# Peripherals.net
KiCad netlist of a schematic drawn in Altium Designer
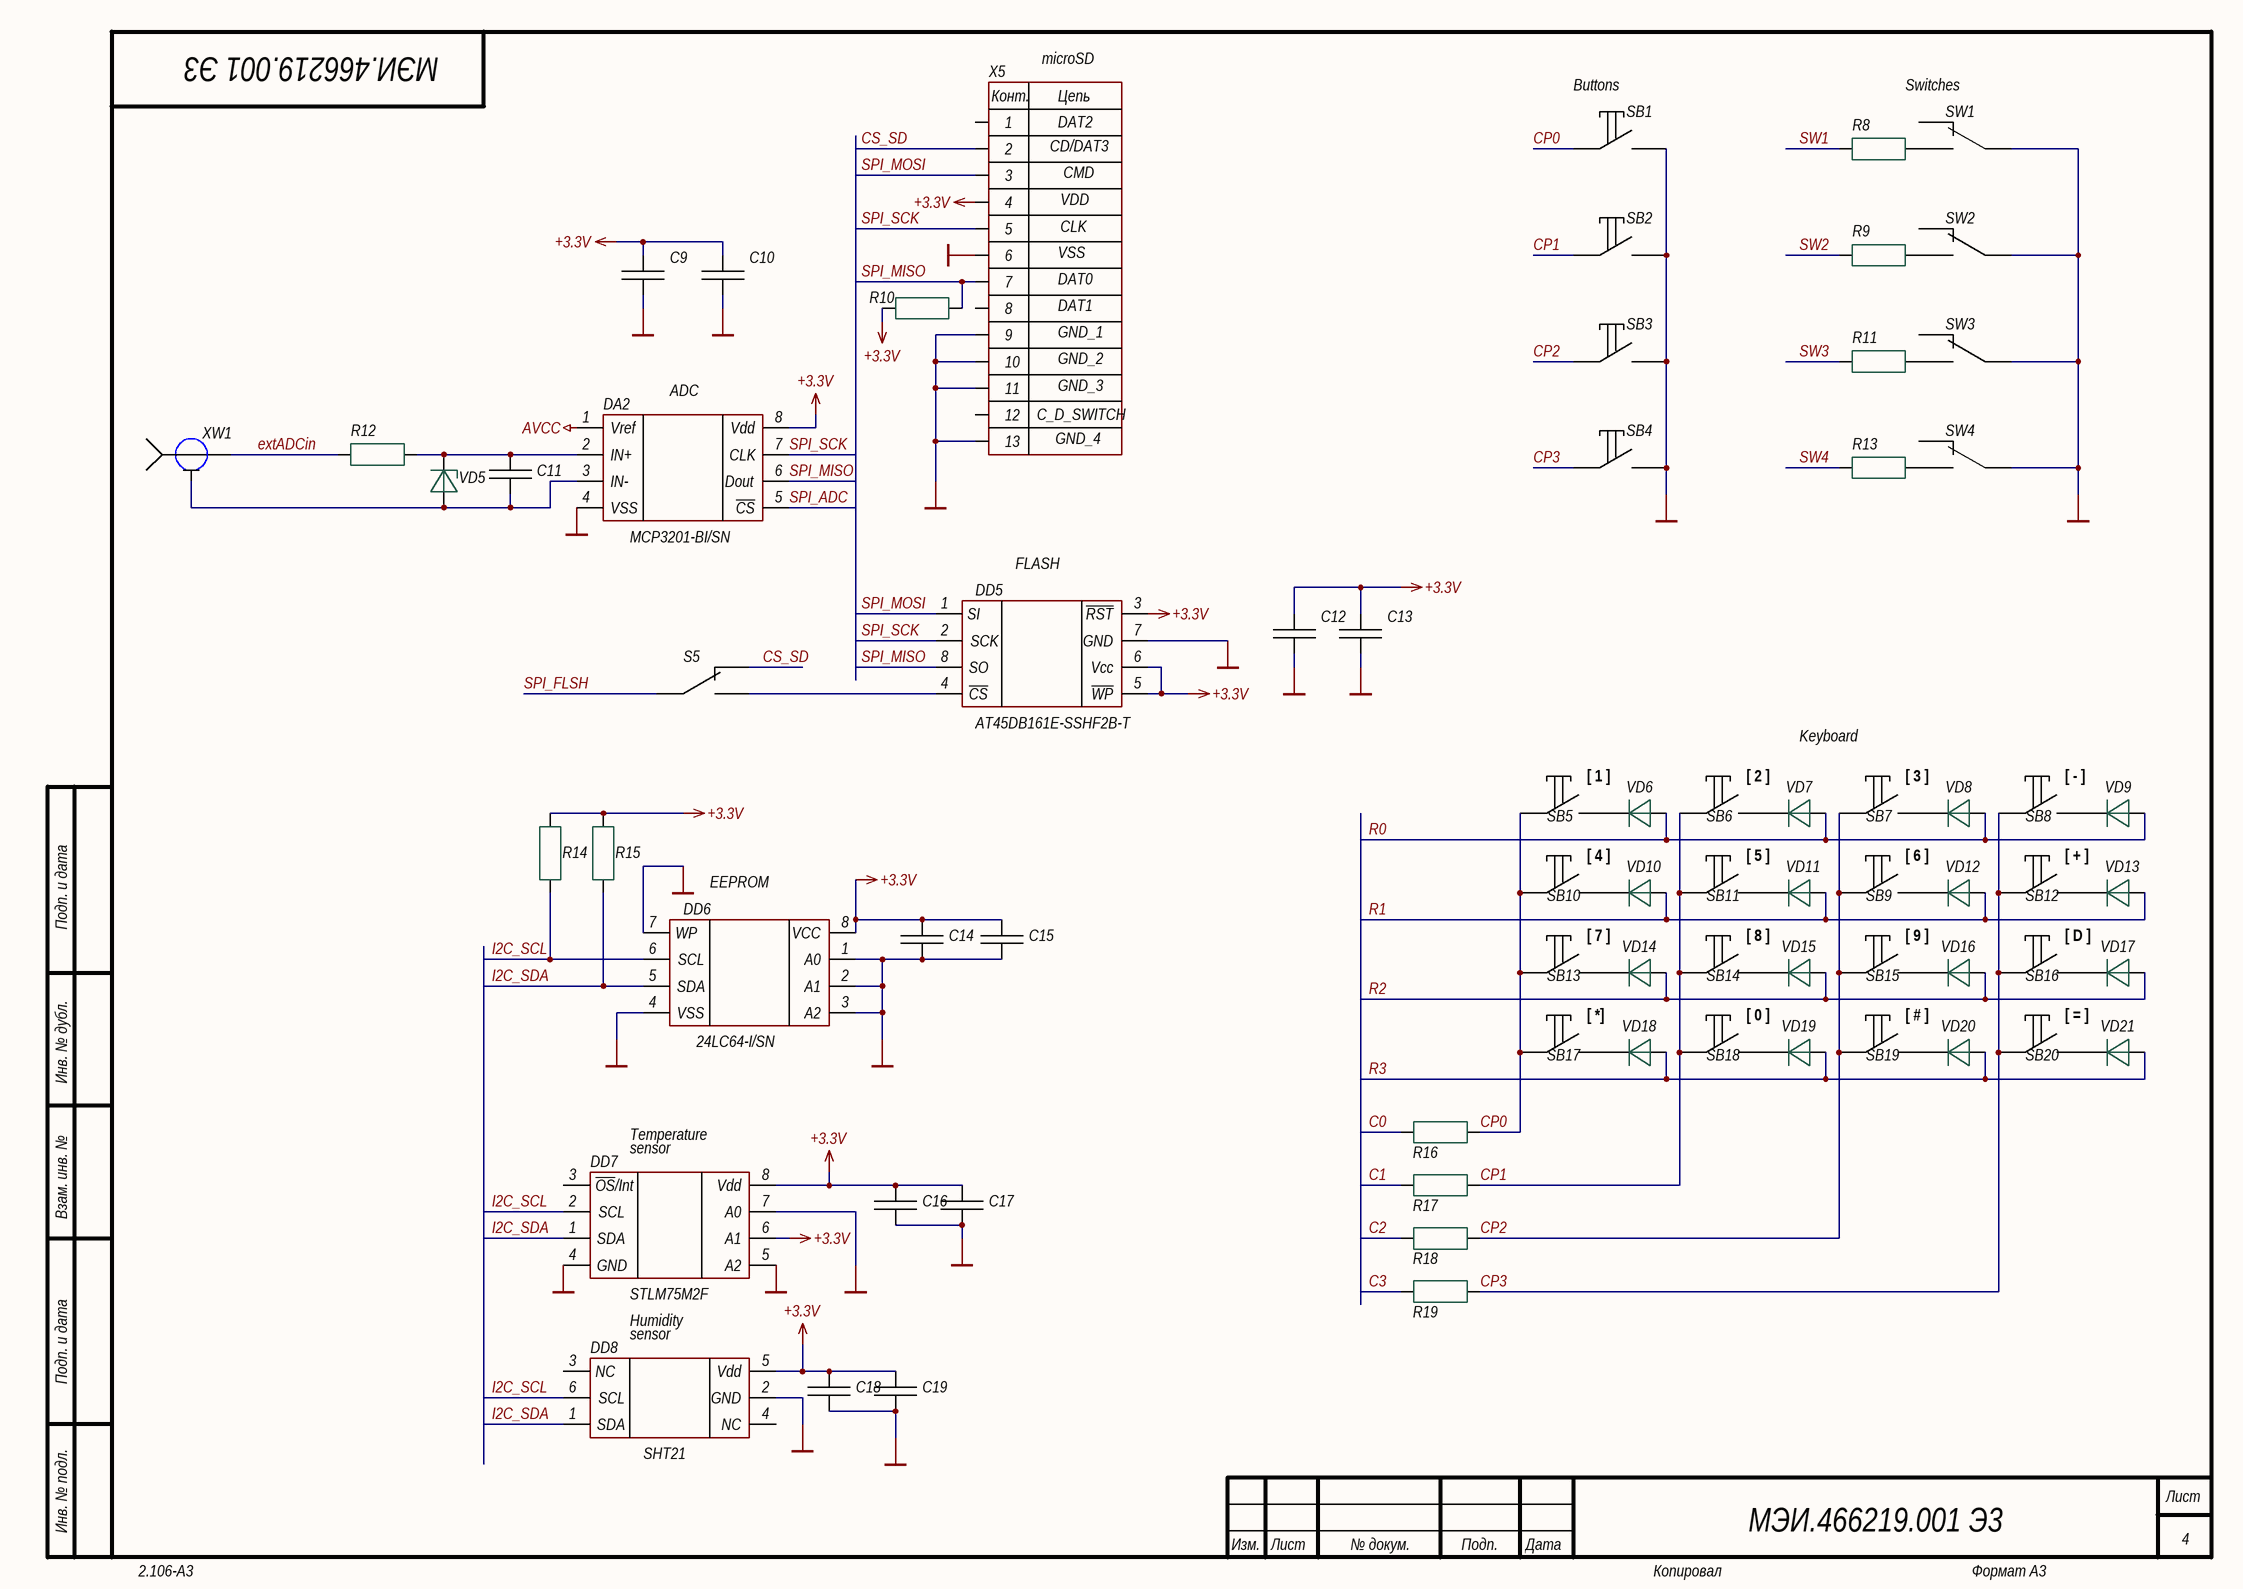
[diagram p0: Peripherals.SchDoc]

(export (version "E")
  (design (tool "Eeschema 10.0.6"))
  (components
    (comp (ref "C9")
      (value "approved sub OK")
      (footprint "CAPC1608X90N")
      (description "Capacitor SMD Cer 100nF 10% 50V X7R 0603")
      (fields (field (name "TOLERANCE") "±10%"))
      (libsource (lib "PBL - Capacitors") (part "CAPC_100n_0603_X7R_50V_10%"))
    )
    (comp (ref "C10")
      (value "approved sub OK")
      (footprint "PBL - SMD Packages:CAPC1608X90N")
      (description "Capacitor SMD Cer 10uF 10% 10V X5R 0603")
      (fields (field (name "TOLERANCE") "±10%"))
      (libsource (lib "PBL - Capacitors") (part "CAPC_10u_0805_10V"))
    )
    (comp (ref "C11")
      (value "approved sub OK")
      (footprint "CAPC2012X135N")
      (description "Capacitor SMD Cer 330nF 10% 25V X7R 0805")
      (fields (field (name "TOLERANCE") "±10%"))
      (libsource (lib "PBL - Capacitors") (part "CAPC_330n_0805_X7R_25V_10%"))
    )
    (comp (ref "C12")
      (value "approved sub OK")
      (footprint "CAPC1608X90N")
      (description "Capacitor SMD Cer 100nF 10% 50V X7R 0603")
      (fields (field (name "TOLERANCE") "±10%"))
      (libsource (lib "PBL - Capacitors") (part "CAPC_100n_0603_X7R_50V_10%"))
    )
    (comp (ref "C13")
      (value "approved sub OK")
      (footprint "PBL - SMD Packages:CAPC1608X90N")
      (description "Capacitor SMD Cer 10uF 10% 10V X5R 0603")
      (fields (field (name "TOLERANCE") "±10%"))
      (libsource (lib "PBL - Capacitors") (part "CAPC_10u_0805_10V"))
    )
    (comp (ref "C14")
      (value "approved sub OK")
      (footprint "CAPC1608X90N")
      (description "Capacitor SMD Cer 100nF 10% 50V X7R 0603")
      (fields (field (name "TOLERANCE") "±10%"))
      (libsource (lib "PBL - Capacitors") (part "CAPC_100n_0603_X7R_50V_10%"))
    )
    (comp (ref "C15")
      (value "approved sub OK")
      (footprint "PBL - SMD Packages:CAPC1608X90N")
      (description "Capacitor SMD Cer 10uF 10% 10V X5R 0603")
      (fields (field (name "TOLERANCE") "±10%"))
      (libsource (lib "PBL - Capacitors") (part "CAPC_10u_0805_10V"))
    )
    (comp (ref "C16")
      (value "approved sub OK")
      (footprint "CAPC1608X90N")
      (description "Capacitor SMD Cer 100nF 10% 50V X7R 0603")
      (fields (field (name "TOLERANCE") "±10%"))
      (libsource (lib "PBL - Capacitors") (part "CAPC_100n_0603_X7R_50V_10%"))
    )
    (comp (ref "C17")
      (value "approved sub OK")
      (footprint "PBL - SMD Packages:CAPC1608X90N")
      (description "Capacitor SMD Cer 10uF 10% 10V X5R 0603")
      (fields (field (name "TOLERANCE") "±10%"))
      (libsource (lib "PBL - Capacitors") (part "CAPC_10u_0805_10V"))
    )
    (comp (ref "C18")
      (value "approved sub OK")
      (footprint "CAPC1608X90N")
      (description "Capacitor SMD Cer 100nF 10% 50V X7R 0603")
      (fields (field (name "TOLERANCE") "±10%"))
      (libsource (lib "PBL - Capacitors") (part "CAPC_100n_0603_X7R_50V_10%"))
    )
    (comp (ref "C19")
      (value "approved sub OK")
      (footprint "PBL - SMD Packages:CAPC1608X90N")
      (description "Capacitor SMD Cer 10uF 10% 10V X5R 0603")
      (fields (field (name "TOLERANCE") "±10%"))
      (libsource (lib "PBL - Capacitors") (part "CAPC_10u_0805_10V"))
    )
    (comp (ref "DA2")
      (value "MCP3201-BI/SN")
      (footprint "PBL - SMD Packages:SOIC127P600X175-8AN")
      (description "ADC")
      (fields (field (name "MODEL") "MCP3201-BI/SN"))
      (libsource (lib "LeSta") (part "MCP3201"))
    )
    (comp (ref "DD5")
      (value "AT45DB161E-SSHF2B-T")
      (footprint "PBL - SMD Packages:SOIC127P600X175-8AN")
      (description "FLASH")
      (fields (field (name "MODEL") "AT45DB161E-SSHF2B-T"))
      (libsource (lib "LeSta") (part "AT45DB161E"))
    )
    (comp (ref "DD6")
      (value "24LC64-I/SN")
      (footprint "PBL - SMD Packages:SOIC127P600X175-8AN")
      (description "EEPROM")
      (fields (field (name "MODEL") "24LC64-I/SN"))
      (libsource (lib "LeSta") (part "24LC64"))
    )
    (comp (ref "DD7")
      (value "STLM75M2F")
      (footprint "PBL - SMD Packages:SOIC127P600X175-8AN")
      (description "Temperature sensor")
      (fields (field (name "MODEL") "STLM75M2F"))
      (libsource (lib "LeSta") (part "STLM75"))
    )
    (comp (ref "DD8")
      (value "SHT21")
      (footprint "LeSta:DFN-6")
      (description "Humidity sensor")
      (fields (field (name "MODEL") "SHT21"))
      (libsource (lib "LeSta") (part "SHT21"))
    )
    (comp (ref "R8")
      (value "RC0603FR-071KL")
      (footprint "RESC1608X55N")
      (description "Resistor SMD chip 1k Ohm 0.1W 1% 0603")
      (fields (field (name "TOLERANCE") "±1%"))
      (libsource (lib "PBL - Resistors") (part "RES_1K_0603_1%"))
    )
    (comp (ref "R9")
      (value "RC0603FR-071KL")
      (footprint "RESC1608X55N")
      (description "Resistor SMD chip 1k Ohm 0.1W 1% 0603")
      (fields (field (name "TOLERANCE") "±1%"))
      (libsource (lib "PBL - Resistors") (part "RES_1K_0603_1%"))
    )
    (comp (ref "R10")
      (value "Thick Film")
      (footprint "RESC1608X55N")
      (description "Resistor SMD chip 10k Ohm 0.1W 1% 0603")
      (fields (field (name "TOLERANCE") "±1%"))
      (libsource (lib "PBL - Resistors") (part "RES_10K_0603_1%"))
    )
    (comp (ref "R11")
      (value "RC0603FR-071KL")
      (footprint "RESC1608X55N")
      (description "Resistor SMD chip 1k Ohm 0.1W 1% 0603")
      (fields (field (name "TOLERANCE") "±1%"))
      (libsource (lib "PBL - Resistors") (part "RES_1K_0603_1%"))
    )
    (comp (ref "R12")
      (value "RC0603FR-071KL")
      (footprint "RESC1608X55N")
      (description "Resistor SMD chip 1k Ohm 0.1W 1% 0603")
      (fields (field (name "TOLERANCE") "±1%"))
      (libsource (lib "PBL - Resistors") (part "RES_1K_0603_1%"))
    )
    (comp (ref "R13")
      (value "RC0603FR-071KL")
      (footprint "RESC1608X55N")
      (description "Resistor SMD chip 1k Ohm 0.1W 1% 0603")
      (fields (field (name "TOLERANCE") "±1%"))
      (libsource (lib "PBL - Resistors") (part "RES_1K_0603_1%"))
    )
    (comp (ref "R14")
      (value "Thick Film")
      (footprint "RESC1608X55N")
      (description "Resistor SMD chip 4.7K Ohm 0.1W 1% 0603")
      (fields (field (name "TOLERANCE") "±1%"))
      (libsource (lib "PBL - Resistors") (part "RES_4K7_0603_1%"))
    )
    (comp (ref "R15")
      (value "Thick Film")
      (footprint "RESC1608X55N")
      (description "Resistor SMD chip 4.7K Ohm 0.1W 1% 0603")
      (fields (field (name "TOLERANCE") "±1%"))
      (libsource (lib "PBL - Resistors") (part "RES_4K7_0603_1%"))
    )
    (comp (ref "R16")
      (value "RC0603FR-071KL")
      (footprint "RESC1608X55N")
      (description "Resistor SMD chip 1k Ohm 0.1W 1% 0603")
      (fields (field (name "TOLERANCE") "±1%"))
      (libsource (lib "PBL - Resistors") (part "RES_1K_0603_1%"))
    )
    (comp (ref "R17")
      (value "RC0603FR-071KL")
      (footprint "RESC1608X55N")
      (description "Resistor SMD chip 1k Ohm 0.1W 1% 0603")
      (fields (field (name "TOLERANCE") "±1%"))
      (libsource (lib "PBL - Resistors") (part "RES_1K_0603_1%"))
    )
    (comp (ref "R18")
      (value "RC0603FR-071KL")
      (footprint "RESC1608X55N")
      (description "Resistor SMD chip 1k Ohm 0.1W 1% 0603")
      (fields (field (name "TOLERANCE") "±1%"))
      (libsource (lib "PBL - Resistors") (part "RES_1K_0603_1%"))
    )
    (comp (ref "R19")
      (value "RC0603FR-071KL")
      (footprint "RESC1608X55N")
      (description "Resistor SMD chip 1k Ohm 0.1W 1% 0603")
      (fields (field (name "TOLERANCE") "±1%"))
      (libsource (lib "PBL - Resistors") (part "RES_1K_0603_1%"))
    )
    (comp (ref "S5")
      (value "ON-ON")
      (footprint "SWITCH_SPDT_SLIDER")
      (description "Switch THD vertical toggle SPDT")
      (libsource (lib "PBL - Switches") (part "SW_THD_SPDT_On-On"))
    )
    (comp (ref "SB1")
      (value "SW_THT_PB_4.3mm")
      (footprint "TACT-SWITCH-3-1825910-5")
      (description "Switch, tact, 4.3mm stem")
      (libsource (lib "PBL - Switches") (part "SW_THT_PB_4.3mm"))
    )
    (comp (ref "SB2")
      (value "SW_THT_PB_4.3mm")
      (footprint "TACT-SWITCH-3-1825910-5")
      (description "Switch, tact, 4.3mm stem")
      (libsource (lib "PBL - Switches") (part "SW_THT_PB_4.3mm"))
    )
    (comp (ref "SB3")
      (value "SW_THT_PB_4.3mm")
      (footprint "TACT-SWITCH-3-1825910-5")
      (description "Switch, tact, 4.3mm stem")
      (libsource (lib "PBL - Switches") (part "SW_THT_PB_4.3mm"))
    )
    (comp (ref "SB4")
      (value "SW_THT_PB_4.3mm")
      (footprint "TACT-SWITCH-3-1825910-5")
      (description "Switch, tact, 4.3mm stem")
      (libsource (lib "PBL - Switches") (part "SW_THT_PB_4.3mm"))
    )
    (comp (ref "SB5")
      (value "SW_THT_PB_4.3mm")
      (footprint "TACT-SWITCH-3-1825910-5")
      (description "Switch, tact, 4.3mm stem")
      (libsource (lib "PBL - Switches") (part "SW_THT_PB_4.3mm"))
    )
    (comp (ref "SB6")
      (value "SW_THT_PB_4.3mm")
      (footprint "TACT-SWITCH-3-1825910-5")
      (description "Switch, tact, 4.3mm stem")
      (libsource (lib "PBL - Switches") (part "SW_THT_PB_4.3mm"))
    )
    (comp (ref "SB7")
      (value "SW_THT_PB_4.3mm")
      (footprint "TACT-SWITCH-3-1825910-5")
      (description "Switch, tact, 4.3mm stem")
      (libsource (lib "PBL - Switches") (part "SW_THT_PB_4.3mm"))
    )
    (comp (ref "SB8")
      (value "SW_THT_PB_4.3mm")
      (footprint "TACT-SWITCH-3-1825910-5")
      (description "Switch, tact, 4.3mm stem")
      (libsource (lib "PBL - Switches") (part "SW_THT_PB_4.3mm"))
    )
    (comp (ref "SB9")
      (value "SW_THT_PB_4.3mm")
      (footprint "TACT-SWITCH-3-1825910-5")
      (description "Switch, tact, 4.3mm stem")
      (libsource (lib "PBL - Switches") (part "SW_THT_PB_4.3mm"))
    )
    (comp (ref "SB10")
      (value "SW_THT_PB_4.3mm")
      (footprint "TACT-SWITCH-3-1825910-5")
      (description "Switch, tact, 4.3mm stem")
      (libsource (lib "PBL - Switches") (part "SW_THT_PB_4.3mm"))
    )
    (comp (ref "SB11")
      (value "SW_THT_PB_4.3mm")
      (footprint "TACT-SWITCH-3-1825910-5")
      (description "Switch, tact, 4.3mm stem")
      (libsource (lib "PBL - Switches") (part "SW_THT_PB_4.3mm"))
    )
    (comp (ref "SB12")
      (value "SW_THT_PB_4.3mm")
      (footprint "TACT-SWITCH-3-1825910-5")
      (description "Switch, tact, 4.3mm stem")
      (libsource (lib "PBL - Switches") (part "SW_THT_PB_4.3mm"))
    )
    (comp (ref "SB13")
      (value "SW_THT_PB_4.3mm")
      (footprint "TACT-SWITCH-3-1825910-5")
      (description "Switch, tact, 4.3mm stem")
      (libsource (lib "PBL - Switches") (part "SW_THT_PB_4.3mm"))
    )
    (comp (ref "SB14")
      (value "SW_THT_PB_4.3mm")
      (footprint "TACT-SWITCH-3-1825910-5")
      (description "Switch, tact, 4.3mm stem")
      (libsource (lib "PBL - Switches") (part "SW_THT_PB_4.3mm"))
    )
    (comp (ref "SB15")
      (value "SW_THT_PB_4.3mm")
      (footprint "TACT-SWITCH-3-1825910-5")
      (description "Switch, tact, 4.3mm stem")
      (libsource (lib "PBL - Switches") (part "SW_THT_PB_4.3mm"))
    )
    (comp (ref "SB16")
      (value "SW_THT_PB_4.3mm")
      (footprint "TACT-SWITCH-3-1825910-5")
      (description "Switch, tact, 4.3mm stem")
      (libsource (lib "PBL - Switches") (part "SW_THT_PB_4.3mm"))
    )
    (comp (ref "SB17")
      (value "SW_THT_PB_4.3mm")
      (footprint "TACT-SWITCH-3-1825910-5")
      (description "Switch, tact, 4.3mm stem")
      (libsource (lib "PBL - Switches") (part "SW_THT_PB_4.3mm"))
    )
    (comp (ref "SB18")
      (value "SW_THT_PB_4.3mm")
      (footprint "TACT-SWITCH-3-1825910-5")
      (description "Switch, tact, 4.3mm stem")
      (libsource (lib "PBL - Switches") (part "SW_THT_PB_4.3mm"))
    )
    (comp (ref "SB19")
      (value "SW_THT_PB_4.3mm")
      (footprint "TACT-SWITCH-3-1825910-5")
      (description "Switch, tact, 4.3mm stem")
      (libsource (lib "PBL - Switches") (part "SW_THT_PB_4.3mm"))
    )
    (comp (ref "SB20")
      (value "SW_THT_PB_4.3mm")
      (footprint "TACT-SWITCH-3-1825910-5")
      (description "Switch, tact, 4.3mm stem")
      (libsource (lib "PBL - Switches") (part "SW_THT_PB_4.3mm"))
    )
    (comp (ref "SW1")
      (value "ON-ON")
      (footprint "SWITCH_SPDT_SLIDER")
      (description "Switch THD vertical toggle SPDT")
      (libsource (lib "PBL - Switches") (part "SW_THD_SPDT_On-On"))
    )
    (comp (ref "SW2")
      (value "ON-ON")
      (footprint "SWITCH_SPDT_SLIDER")
      (description "Switch THD vertical toggle SPDT")
      (libsource (lib "PBL - Switches") (part "SW_THD_SPDT_On-On"))
    )
    (comp (ref "SW3")
      (value "ON-ON")
      (footprint "SWITCH_SPDT_SLIDER")
      (description "Switch THD vertical toggle SPDT")
      (libsource (lib "PBL - Switches") (part "SW_THD_SPDT_On-On"))
    )
    (comp (ref "SW4")
      (value "ON-ON")
      (footprint "SWITCH_SPDT_SLIDER")
      (description "Switch THD vertical toggle SPDT")
      (libsource (lib "PBL - Switches") (part "SW_THD_SPDT_On-On"))
    )
    (comp (ref "VD5")
      (value "4V")
      (footprint "SOD323")
      (description "Diode Zener SMD 4V 200mW SOD-323")
      (fields (field (name "TOLERANCE") "±3%"))
      (libsource (lib "PBL - Diodes") (part "DIODE_ZENER_4V_SOD323"))
    )
    (comp (ref "VD6")
      (value "1N4148")
      (footprint "SOD523F")
      (description "Diode SMD small signal 0.2A SOD-523F")
      (libsource (lib "PBL - Diodes") (part "DIODE_1N4148_200mA_SOD523F"))
    )
    (comp (ref "VD7")
      (value "1N4148")
      (footprint "SOD523F")
      (description "Diode SMD small signal 0.2A SOD-523F")
      (libsource (lib "PBL - Diodes") (part "DIODE_1N4148_200mA_SOD523F"))
    )
    (comp (ref "VD8")
      (value "1N4148")
      (footprint "SOD523F")
      (description "Diode SMD small signal 0.2A SOD-523F")
      (libsource (lib "PBL - Diodes") (part "DIODE_1N4148_200mA_SOD523F"))
    )
    (comp (ref "VD9")
      (value "1N4148")
      (footprint "SOD523F")
      (description "Diode SMD small signal 0.2A SOD-523F")
      (libsource (lib "PBL - Diodes") (part "DIODE_1N4148_200mA_SOD523F"))
    )
    (comp (ref "VD10")
      (value "1N4148")
      (footprint "SOD523F")
      (description "Diode SMD small signal 0.2A SOD-523F")
      (libsource (lib "PBL - Diodes") (part "DIODE_1N4148_200mA_SOD523F"))
    )
    (comp (ref "VD11")
      (value "1N4148")
      (footprint "SOD523F")
      (description "Diode SMD small signal 0.2A SOD-523F")
      (libsource (lib "PBL - Diodes") (part "DIODE_1N4148_200mA_SOD523F"))
    )
    (comp (ref "VD12")
      (value "1N4148")
      (footprint "SOD523F")
      (description "Diode SMD small signal 0.2A SOD-523F")
      (libsource (lib "PBL - Diodes") (part "DIODE_1N4148_200mA_SOD523F"))
    )
    (comp (ref "VD13")
      (value "1N4148")
      (footprint "SOD523F")
      (description "Diode SMD small signal 0.2A SOD-523F")
      (libsource (lib "PBL - Diodes") (part "DIODE_1N4148_200mA_SOD523F"))
    )
    (comp (ref "VD14")
      (value "1N4148")
      (footprint "SOD523F")
      (description "Diode SMD small signal 0.2A SOD-523F")
      (libsource (lib "PBL - Diodes") (part "DIODE_1N4148_200mA_SOD523F"))
    )
    (comp (ref "VD15")
      (value "1N4148")
      (footprint "SOD523F")
      (description "Diode SMD small signal 0.2A SOD-523F")
      (libsource (lib "PBL - Diodes") (part "DIODE_1N4148_200mA_SOD523F"))
    )
    (comp (ref "VD16")
      (value "1N4148")
      (footprint "SOD523F")
      (description "Diode SMD small signal 0.2A SOD-523F")
      (libsource (lib "PBL - Diodes") (part "DIODE_1N4148_200mA_SOD523F"))
    )
    (comp (ref "VD17")
      (value "1N4148")
      (footprint "SOD523F")
      (description "Diode SMD small signal 0.2A SOD-523F")
      (libsource (lib "PBL - Diodes") (part "DIODE_1N4148_200mA_SOD523F"))
    )
    (comp (ref "VD18")
      (value "1N4148")
      (footprint "SOD523F")
      (description "Diode SMD small signal 0.2A SOD-523F")
      (libsource (lib "PBL - Diodes") (part "DIODE_1N4148_200mA_SOD523F"))
    )
    (comp (ref "VD19")
      (value "1N4148")
      (footprint "SOD523F")
      (description "Diode SMD small signal 0.2A SOD-523F")
      (libsource (lib "PBL - Diodes") (part "DIODE_1N4148_200mA_SOD523F"))
    )
    (comp (ref "VD20")
      (value "1N4148")
      (footprint "SOD523F")
      (description "Diode SMD small signal 0.2A SOD-523F")
      (libsource (lib "PBL - Diodes") (part "DIODE_1N4148_200mA_SOD523F"))
    )
    (comp (ref "VD21")
      (value "1N4148")
      (footprint "SOD523F")
      (description "Diode SMD small signal 0.2A SOD-523F")
      (libsource (lib "PBL - Diodes") (part "DIODE_1N4148_200mA_SOD523F"))
    )
    (comp (ref "X5")
      (value "DM3CS-SF")
      (footprint "SamacSys:DM3CS-SF")
      (description "Connector")
      (fields (field (name "MOUSER2 PART NUMBER") "798-DM3CSSF"))
      (libsource (lib "LeSta") (part "DM3CS-SF"))
    )
    (comp (ref "XW1")
      (value "BNC Fem. 50R")
      (footprint "LeSta:BNC")
      (description "BNC")
      (libsource (lib "PBL - Connectors") (part "CONN_BNC"))
    )
  )
  (nets
    (net (code "1") (name "+3.3V") (class "Default")
      (node (ref "C10") (pin "1") (pintype "passive"))
      (node (ref "C12") (pin "1") (pintype "passive"))
      (node (ref "C13") (pin "1") (pintype "passive"))
      (node (ref "C14") (pin "1") (pintype "passive"))
      (node (ref "C15") (pin "1") (pintype "passive"))
      (node (ref "C16") (pin "1") (pintype "passive"))
      (node (ref "C17") (pin "1") (pintype "passive"))
      (node (ref "C18") (pin "1") (pintype "passive"))
      (node (ref "C19") (pin "1") (pintype "passive"))
      (node (ref "C9") (pin "1") (pintype "passive"))
      (node (ref "DA2") (pin "8") (pinfunction "Vdd_8") (pintype "passive"))
      (node (ref "DD5") (pin "3") (pinfunction "~{RST}_3") (pintype "passive"))
      (node (ref "DD5") (pin "5") (pinfunction "~{WP}_5") (pintype "passive"))
      (node (ref "DD5") (pin "6") (pinfunction "Vcc_6") (pintype "passive"))
      (node (ref "DD6") (pin "8") (pinfunction "VCC_8") (pintype "passive"))
      (node (ref "DD7") (pin "6") (pinfunction "A1_6") (pintype "passive"))
      (node (ref "DD7") (pin "8") (pinfunction "Vdd_8") (pintype "passive"))
      (node (ref "DD8") (pin "5") (pinfunction "Vdd_5") (pintype "passive"))
      (node (ref "R10") (pin "1") (pinfunction "1_1") (pintype "passive"))
      (node (ref "R14") (pin "2") (pinfunction "2_2") (pintype "passive"))
      (node (ref "R15") (pin "2") (pinfunction "2_2") (pintype "passive"))
      (node (ref "X5") (pin "4") (pinfunction "4_4") (pintype "passive"))
    )
    (net (code "2") (name "/C0") (class "Default")
      (node (ref "R16") (pin "1") (pinfunction "1_1") (pintype "passive"))
    )
    (net (code "3") (name "/C1") (class "Default")
      (node (ref "R17") (pin "1") (pinfunction "1_1") (pintype "passive"))
    )
    (net (code "4") (name "/C2") (class "Default")
      (node (ref "R18") (pin "1") (pinfunction "1_1") (pintype "passive"))
    )
    (net (code "5") (name "/C3") (class "Default")
      (node (ref "R19") (pin "1") (pinfunction "1_1") (pintype "passive"))
    )
    (net (code "6") (name "/CP0") (class "Default")
      (node (ref "R16") (pin "2") (pinfunction "2_2") (pintype "passive"))
      (node (ref "SB1") (pin "1") (pinfunction "1_1") (pintype "passive"))
      (node (ref "SB10") (pin "1") (pinfunction "1_1") (pintype "passive"))
      (node (ref "SB13") (pin "1") (pinfunction "1_1") (pintype "passive"))
      (node (ref "SB17") (pin "1") (pinfunction "1_1") (pintype "passive"))
      (node (ref "SB5") (pin "1") (pinfunction "1_1") (pintype "passive"))
    )
    (net (code "7") (name "/CP1") (class "Default")
      (node (ref "R17") (pin "2") (pinfunction "2_2") (pintype "passive"))
      (node (ref "SB11") (pin "1") (pinfunction "1_1") (pintype "passive"))
      (node (ref "SB14") (pin "1") (pinfunction "1_1") (pintype "passive"))
      (node (ref "SB18") (pin "1") (pinfunction "1_1") (pintype "passive"))
      (node (ref "SB2") (pin "1") (pinfunction "1_1") (pintype "passive"))
      (node (ref "SB6") (pin "1") (pinfunction "1_1") (pintype "passive"))
    )
    (net (code "8") (name "/CP2") (class "Default")
      (node (ref "R18") (pin "2") (pinfunction "2_2") (pintype "passive"))
      (node (ref "SB15") (pin "1") (pinfunction "1_1") (pintype "passive"))
      (node (ref "SB19") (pin "1") (pinfunction "1_1") (pintype "passive"))
      (node (ref "SB3") (pin "1") (pinfunction "1_1") (pintype "passive"))
      (node (ref "SB7") (pin "1") (pinfunction "1_1") (pintype "passive"))
      (node (ref "SB9") (pin "1") (pinfunction "1_1") (pintype "passive"))
    )
    (net (code "9") (name "/CP3") (class "Default")
      (node (ref "R19") (pin "2") (pinfunction "2_2") (pintype "passive"))
      (node (ref "SB12") (pin "1") (pinfunction "1_1") (pintype "passive"))
      (node (ref "SB16") (pin "1") (pinfunction "1_1") (pintype "passive"))
      (node (ref "SB20") (pin "1") (pinfunction "1_1") (pintype "passive"))
      (node (ref "SB4") (pin "1") (pinfunction "1_1") (pintype "passive"))
      (node (ref "SB8") (pin "1") (pinfunction "1_1") (pintype "passive"))
    )
    (net (code "10") (name "/CS_SD") (class "Default")
      (node (ref "S5") (pin "3") (pinfunction "3_3") (pintype "passive"))
      (node (ref "X5") (pin "2") (pinfunction "2_2") (pintype "passive"))
    )
    (net (code "11") (name "/I2C_SCL") (class "Default")
      (node (ref "DD6") (pin "6") (pinfunction "SCL_6") (pintype "passive"))
      (node (ref "DD7") (pin "2") (pinfunction "SCL_2") (pintype "passive"))
      (node (ref "DD8") (pin "6") (pinfunction "SCL_6") (pintype "passive"))
      (node (ref "R14") (pin "1") (pinfunction "1_1") (pintype "passive"))
    )
    (net (code "12") (name "/I2C_SDA") (class "Default")
      (node (ref "DD6") (pin "5") (pinfunction "SDA_5") (pintype "passive"))
      (node (ref "DD7") (pin "1") (pinfunction "SDA_1") (pintype "passive"))
      (node (ref "DD8") (pin "1") (pinfunction "SDA_1") (pintype "passive"))
      (node (ref "R15") (pin "1") (pinfunction "1_1") (pintype "passive"))
    )
    (net (code "13") (name "/R0") (class "Default")
      (node (ref "VD6") (pin "A") (pinfunction "A_A") (pintype "passive"))
      (node (ref "VD7") (pin "A") (pinfunction "A_A") (pintype "passive"))
      (node (ref "VD8") (pin "A") (pinfunction "A_A") (pintype "passive"))
      (node (ref "VD9") (pin "A") (pinfunction "A_A") (pintype "passive"))
    )
    (net (code "14") (name "/R1") (class "Default")
      (node (ref "VD10") (pin "A") (pinfunction "A_A") (pintype "passive"))
      (node (ref "VD11") (pin "A") (pinfunction "A_A") (pintype "passive"))
      (node (ref "VD12") (pin "A") (pinfunction "A_A") (pintype "passive"))
      (node (ref "VD13") (pin "A") (pinfunction "A_A") (pintype "passive"))
    )
    (net (code "15") (name "/R2") (class "Default")
      (node (ref "VD14") (pin "A") (pinfunction "A_A") (pintype "passive"))
      (node (ref "VD15") (pin "A") (pinfunction "A_A") (pintype "passive"))
      (node (ref "VD16") (pin "A") (pinfunction "A_A") (pintype "passive"))
      (node (ref "VD17") (pin "A") (pinfunction "A_A") (pintype "passive"))
    )
    (net (code "16") (name "/R3") (class "Default")
      (node (ref "VD18") (pin "A") (pinfunction "A_A") (pintype "passive"))
      (node (ref "VD19") (pin "A") (pinfunction "A_A") (pintype "passive"))
      (node (ref "VD20") (pin "A") (pinfunction "A_A") (pintype "passive"))
      (node (ref "VD21") (pin "A") (pinfunction "A_A") (pintype "passive"))
    )
    (net (code "17") (name "/SPI_ADC") (class "Default")
      (node (ref "DA2") (pin "5") (pinfunction "~{CS}_5") (pintype "passive"))
    )
    (net (code "18") (name "/SPI_FLSH") (class "Default")
      (node (ref "S5") (pin "2") (pinfunction "2_2") (pintype "passive"))
    )
    (net (code "19") (name "/SPI_MISO") (class "Default")
      (node (ref "DA2") (pin "6") (pinfunction "Dout_6") (pintype "passive"))
      (node (ref "DD5") (pin "8") (pinfunction "SO_8") (pintype "passive"))
      (node (ref "R10") (pin "2") (pinfunction "2_2") (pintype "passive"))
      (node (ref "X5") (pin "7") (pinfunction "7_7") (pintype "passive"))
    )
    (net (code "20") (name "/SPI_MOSI") (class "Default")
      (node (ref "DD5") (pin "1") (pinfunction "SI_1") (pintype "passive"))
      (node (ref "X5") (pin "3") (pinfunction "3_3") (pintype "passive"))
    )
    (net (code "21") (name "/SPI_SCK") (class "Default")
      (node (ref "DA2") (pin "7") (pinfunction "CLK_7") (pintype "passive"))
      (node (ref "DD5") (pin "2") (pinfunction "SCK_2") (pintype "passive"))
      (node (ref "X5") (pin "5") (pinfunction "5_5") (pintype "passive"))
    )
    (net (code "22") (name "/SW1") (class "Default")
      (node (ref "R8") (pin "1") (pinfunction "1_1") (pintype "passive"))
    )
    (net (code "23") (name "/SW2") (class "Default")
      (node (ref "R9") (pin "1") (pinfunction "1_1") (pintype "passive"))
    )
    (net (code "24") (name "/SW3") (class "Default")
      (node (ref "R11") (pin "1") (pinfunction "1_1") (pintype "passive"))
    )
    (net (code "25") (name "/SW4") (class "Default")
      (node (ref "R13") (pin "1") (pinfunction "1_1") (pintype "passive"))
    )
    (net (code "26") (name "/extADCin") (class "Default")
      (node (ref "R12") (pin "1") (pinfunction "1_1") (pintype "passive"))
      (node (ref "XW1") (pin "Sig") (pinfunction "Sig_Sig") (pintype "passive"))
    )
    (net (code "27") (name "AVCC") (class "Default")
      (node (ref "DA2") (pin "1") (pinfunction "Vref_1") (pintype "passive"))
    )
    (net (code "28") (name "GND") (class "Default")
      (node (ref "C10") (pin "2") (pintype "passive"))
      (node (ref "C12") (pin "2") (pintype "passive"))
      (node (ref "C13") (pin "2") (pintype "passive"))
      (node (ref "C14") (pin "2") (pintype "passive"))
      (node (ref "C15") (pin "2") (pintype "passive"))
      (node (ref "C16") (pin "2") (pintype "passive"))
      (node (ref "C17") (pin "2") (pintype "passive"))
      (node (ref "C18") (pin "2") (pintype "passive"))
      (node (ref "C19") (pin "2") (pintype "passive"))
      (node (ref "C9") (pin "2") (pintype "passive"))
      (node (ref "DA2") (pin "4") (pinfunction "VSS_4") (pintype "passive"))
      (node (ref "DD5") (pin "7") (pinfunction "GND_7") (pintype "passive"))
      (node (ref "DD6") (pin "1") (pinfunction "A0_1") (pintype "passive"))
      (node (ref "DD6") (pin "2") (pinfunction "A1_2") (pintype "passive"))
      (node (ref "DD6") (pin "3") (pinfunction "A2_3") (pintype "passive"))
      (node (ref "DD6") (pin "4") (pinfunction "VSS_4") (pintype "passive"))
      (node (ref "DD6") (pin "7") (pinfunction "WP_7") (pintype "passive"))
      (node (ref "DD7") (pin "4") (pinfunction "GND_4") (pintype "passive"))
      (node (ref "DD7") (pin "5") (pinfunction "A2_5") (pintype "passive"))
      (node (ref "DD7") (pin "7") (pinfunction "A0_7") (pintype "passive"))
      (node (ref "DD8") (pin "2") (pinfunction "GND_2") (pintype "passive"))
      (node (ref "SB1") (pin "2") (pinfunction "2_2") (pintype "passive"))
      (node (ref "SB2") (pin "2") (pinfunction "2_2") (pintype "passive"))
      (node (ref "SB3") (pin "2") (pinfunction "2_2") (pintype "passive"))
      (node (ref "SB4") (pin "2") (pinfunction "2_2") (pintype "passive"))
      (node (ref "SW1") (pin "2") (pinfunction "2_2") (pintype "passive"))
      (node (ref "SW2") (pin "2") (pinfunction "2_2") (pintype "passive"))
      (node (ref "SW3") (pin "2") (pinfunction "2_2") (pintype "passive"))
      (node (ref "SW4") (pin "2") (pinfunction "2_2") (pintype "passive"))
      (node (ref "X5") (pin "10") (pinfunction "10_10") (pintype "passive"))
      (node (ref "X5") (pin "11") (pinfunction "11_11") (pintype "passive"))
      (node (ref "X5") (pin "13") (pinfunction "13_13") (pintype "passive"))
      (node (ref "X5") (pin "6") (pinfunction "6_6") (pintype "passive"))
      (node (ref "X5") (pin "9") (pinfunction "9_9") (pintype "passive"))
    )
    (net (code "29") (name "Net-(DA2-IN+)") (class "Default")
      (node (ref "C11") (pin "1") (pintype "passive"))
      (node (ref "DA2") (pin "2") (pinfunction "IN+_2") (pintype "passive"))
      (node (ref "R12") (pin "2") (pinfunction "2_2") (pintype "passive"))
      (node (ref "VD5") (pin "K") (pinfunction "K_K") (pintype "passive"))
    )
    (net (code "30") (name "Net-(DA2-IN-)") (class "Default")
      (node (ref "C11") (pin "2") (pintype "passive"))
      (node (ref "DA2") (pin "3") (pinfunction "IN-_3") (pintype "passive"))
      (node (ref "VD5") (pin "A") (pinfunction "A_A") (pintype "passive"))
      (node (ref "XW1") (pin "Case") (pinfunction "Case_Case") (pintype "passive"))
    )
    (net (code "31") (name "Net-(DD5-~{CS})") (class "Default")
      (node (ref "DD5") (pin "4") (pinfunction "~{CS}_4") (pintype "passive"))
      (node (ref "S5") (pin "1") (pinfunction "1_1") (pintype "passive"))
    )
    (net (code "32") (name "Net-(R8-Pad2)") (class "Default")
      (node (ref "R8") (pin "2") (pinfunction "2_2") (pintype "passive"))
      (node (ref "SW1") (pin "1") (pinfunction "1_1") (pintype "passive"))
    )
    (net (code "33") (name "Net-(R9-Pad2)") (class "Default")
      (node (ref "R9") (pin "2") (pinfunction "2_2") (pintype "passive"))
      (node (ref "SW2") (pin "1") (pinfunction "1_1") (pintype "passive"))
    )
    (net (code "34") (name "Net-(R11-Pad2)") (class "Default")
      (node (ref "R11") (pin "2") (pinfunction "2_2") (pintype "passive"))
      (node (ref "SW3") (pin "1") (pinfunction "1_1") (pintype "passive"))
    )
    (net (code "35") (name "Net-(R13-Pad2)") (class "Default")
      (node (ref "R13") (pin "2") (pinfunction "2_2") (pintype "passive"))
      (node (ref "SW4") (pin "1") (pinfunction "1_1") (pintype "passive"))
    )
    (net (code "36") (name "Net-(SB5-Pad2)") (class "Default")
      (node (ref "SB5") (pin "2") (pinfunction "2_2") (pintype "passive"))
      (node (ref "VD6") (pin "K") (pinfunction "K_K") (pintype "passive"))
    )
    (net (code "37") (name "Net-(SB6-Pad2)") (class "Default")
      (node (ref "SB6") (pin "2") (pinfunction "2_2") (pintype "passive"))
      (node (ref "VD7") (pin "K") (pinfunction "K_K") (pintype "passive"))
    )
    (net (code "38") (name "Net-(SB7-Pad2)") (class "Default")
      (node (ref "SB7") (pin "2") (pinfunction "2_2") (pintype "passive"))
      (node (ref "VD8") (pin "K") (pinfunction "K_K") (pintype "passive"))
    )
    (net (code "39") (name "Net-(SB8-Pad2)") (class "Default")
      (node (ref "SB8") (pin "2") (pinfunction "2_2") (pintype "passive"))
      (node (ref "VD9") (pin "K") (pinfunction "K_K") (pintype "passive"))
    )
    (net (code "40") (name "Net-(SB9-Pad2)") (class "Default")
      (node (ref "SB9") (pin "2") (pinfunction "2_2") (pintype "passive"))
      (node (ref "VD12") (pin "K") (pinfunction "K_K") (pintype "passive"))
    )
    (net (code "41") (name "Net-(SB10-Pad2)") (class "Default")
      (node (ref "SB10") (pin "2") (pinfunction "2_2") (pintype "passive"))
      (node (ref "VD10") (pin "K") (pinfunction "K_K") (pintype "passive"))
    )
    (net (code "42") (name "Net-(SB11-Pad2)") (class "Default")
      (node (ref "SB11") (pin "2") (pinfunction "2_2") (pintype "passive"))
      (node (ref "VD11") (pin "K") (pinfunction "K_K") (pintype "passive"))
    )
    (net (code "43") (name "Net-(SB12-Pad2)") (class "Default")
      (node (ref "SB12") (pin "2") (pinfunction "2_2") (pintype "passive"))
      (node (ref "VD13") (pin "K") (pinfunction "K_K") (pintype "passive"))
    )
    (net (code "44") (name "Net-(SB13-Pad2)") (class "Default")
      (node (ref "SB13") (pin "2") (pinfunction "2_2") (pintype "passive"))
      (node (ref "VD14") (pin "K") (pinfunction "K_K") (pintype "passive"))
    )
    (net (code "45") (name "Net-(SB14-Pad2)") (class "Default")
      (node (ref "SB14") (pin "2") (pinfunction "2_2") (pintype "passive"))
      (node (ref "VD15") (pin "K") (pinfunction "K_K") (pintype "passive"))
    )
    (net (code "46") (name "Net-(SB15-Pad2)") (class "Default")
      (node (ref "SB15") (pin "2") (pinfunction "2_2") (pintype "passive"))
      (node (ref "VD16") (pin "K") (pinfunction "K_K") (pintype "passive"))
    )
    (net (code "47") (name "Net-(SB16-Pad2)") (class "Default")
      (node (ref "SB16") (pin "2") (pinfunction "2_2") (pintype "passive"))
      (node (ref "VD17") (pin "K") (pinfunction "K_K") (pintype "passive"))
    )
    (net (code "48") (name "Net-(SB17-Pad2)") (class "Default")
      (node (ref "SB17") (pin "2") (pinfunction "2_2") (pintype "passive"))
      (node (ref "VD18") (pin "K") (pinfunction "K_K") (pintype "passive"))
    )
    (net (code "49") (name "Net-(SB18-Pad2)") (class "Default")
      (node (ref "SB18") (pin "2") (pinfunction "2_2") (pintype "passive"))
      (node (ref "VD19") (pin "K") (pinfunction "K_K") (pintype "passive"))
    )
    (net (code "50") (name "Net-(SB19-Pad2)") (class "Default")
      (node (ref "SB19") (pin "2") (pinfunction "2_2") (pintype "passive"))
      (node (ref "VD20") (pin "K") (pinfunction "K_K") (pintype "passive"))
    )
    (net (code "51") (name "Net-(SB20-Pad2)") (class "Default")
      (node (ref "SB20") (pin "2") (pinfunction "2_2") (pintype "passive"))
      (node (ref "VD21") (pin "K") (pinfunction "K_K") (pintype "passive"))
    )
    (net (code "52") (name "unconnected-(DD7-~{OS}{slash}Int-Pad3)") (class "Default")
      (node (ref "DD7") (pin "3") (pinfunction "~{OS}/Int_3") (pintype "passive"))
    )
    (net (code "53") (name "unconnected-(DD8-NC-Pad3)") (class "Default")
      (node (ref "DD8") (pin "3") (pinfunction "NC_3") (pintype "passive"))
    )
    (net (code "54") (name "unconnected-(DD8-NC-Pad4)") (class "Default")
      (node (ref "DD8") (pin "4") (pinfunction "NC_4") (pintype "passive"))
    )
    (net (code "55") (name "unconnected-(SW1-Pad3)") (class "Default")
      (node (ref "SW1") (pin "3") (pinfunction "3_3") (pintype "passive"))
    )
    (net (code "56") (name "unconnected-(SW2-Pad3)") (class "Default")
      (node (ref "SW2") (pin "3") (pinfunction "3_3") (pintype "passive"))
    )
    (net (code "57") (name "unconnected-(SW3-Pad3)") (class "Default")
      (node (ref "SW3") (pin "3") (pinfunction "3_3") (pintype "passive"))
    )
    (net (code "58") (name "unconnected-(SW4-Pad3)") (class "Default")
      (node (ref "SW4") (pin "3") (pinfunction "3_3") (pintype "passive"))
    )
    (net (code "59") (name "unconnected-(X5-Pad1)") (class "Default")
      (node (ref "X5") (pin "1") (pinfunction "1_1") (pintype "passive"))
    )
    (net (code "60") (name "unconnected-(X5-Pad8)") (class "Default")
      (node (ref "X5") (pin "8") (pinfunction "8_8") (pintype "passive"))
    )
    (net (code "61") (name "unconnected-(X5-Pad12)") (class "Default")
      (node (ref "X5") (pin "12") (pinfunction "12_12") (pintype "passive"))
    )
  )
)
